# WristMountedAvionics.net
KiCad netlist of a schematic drawn in EasyEDA
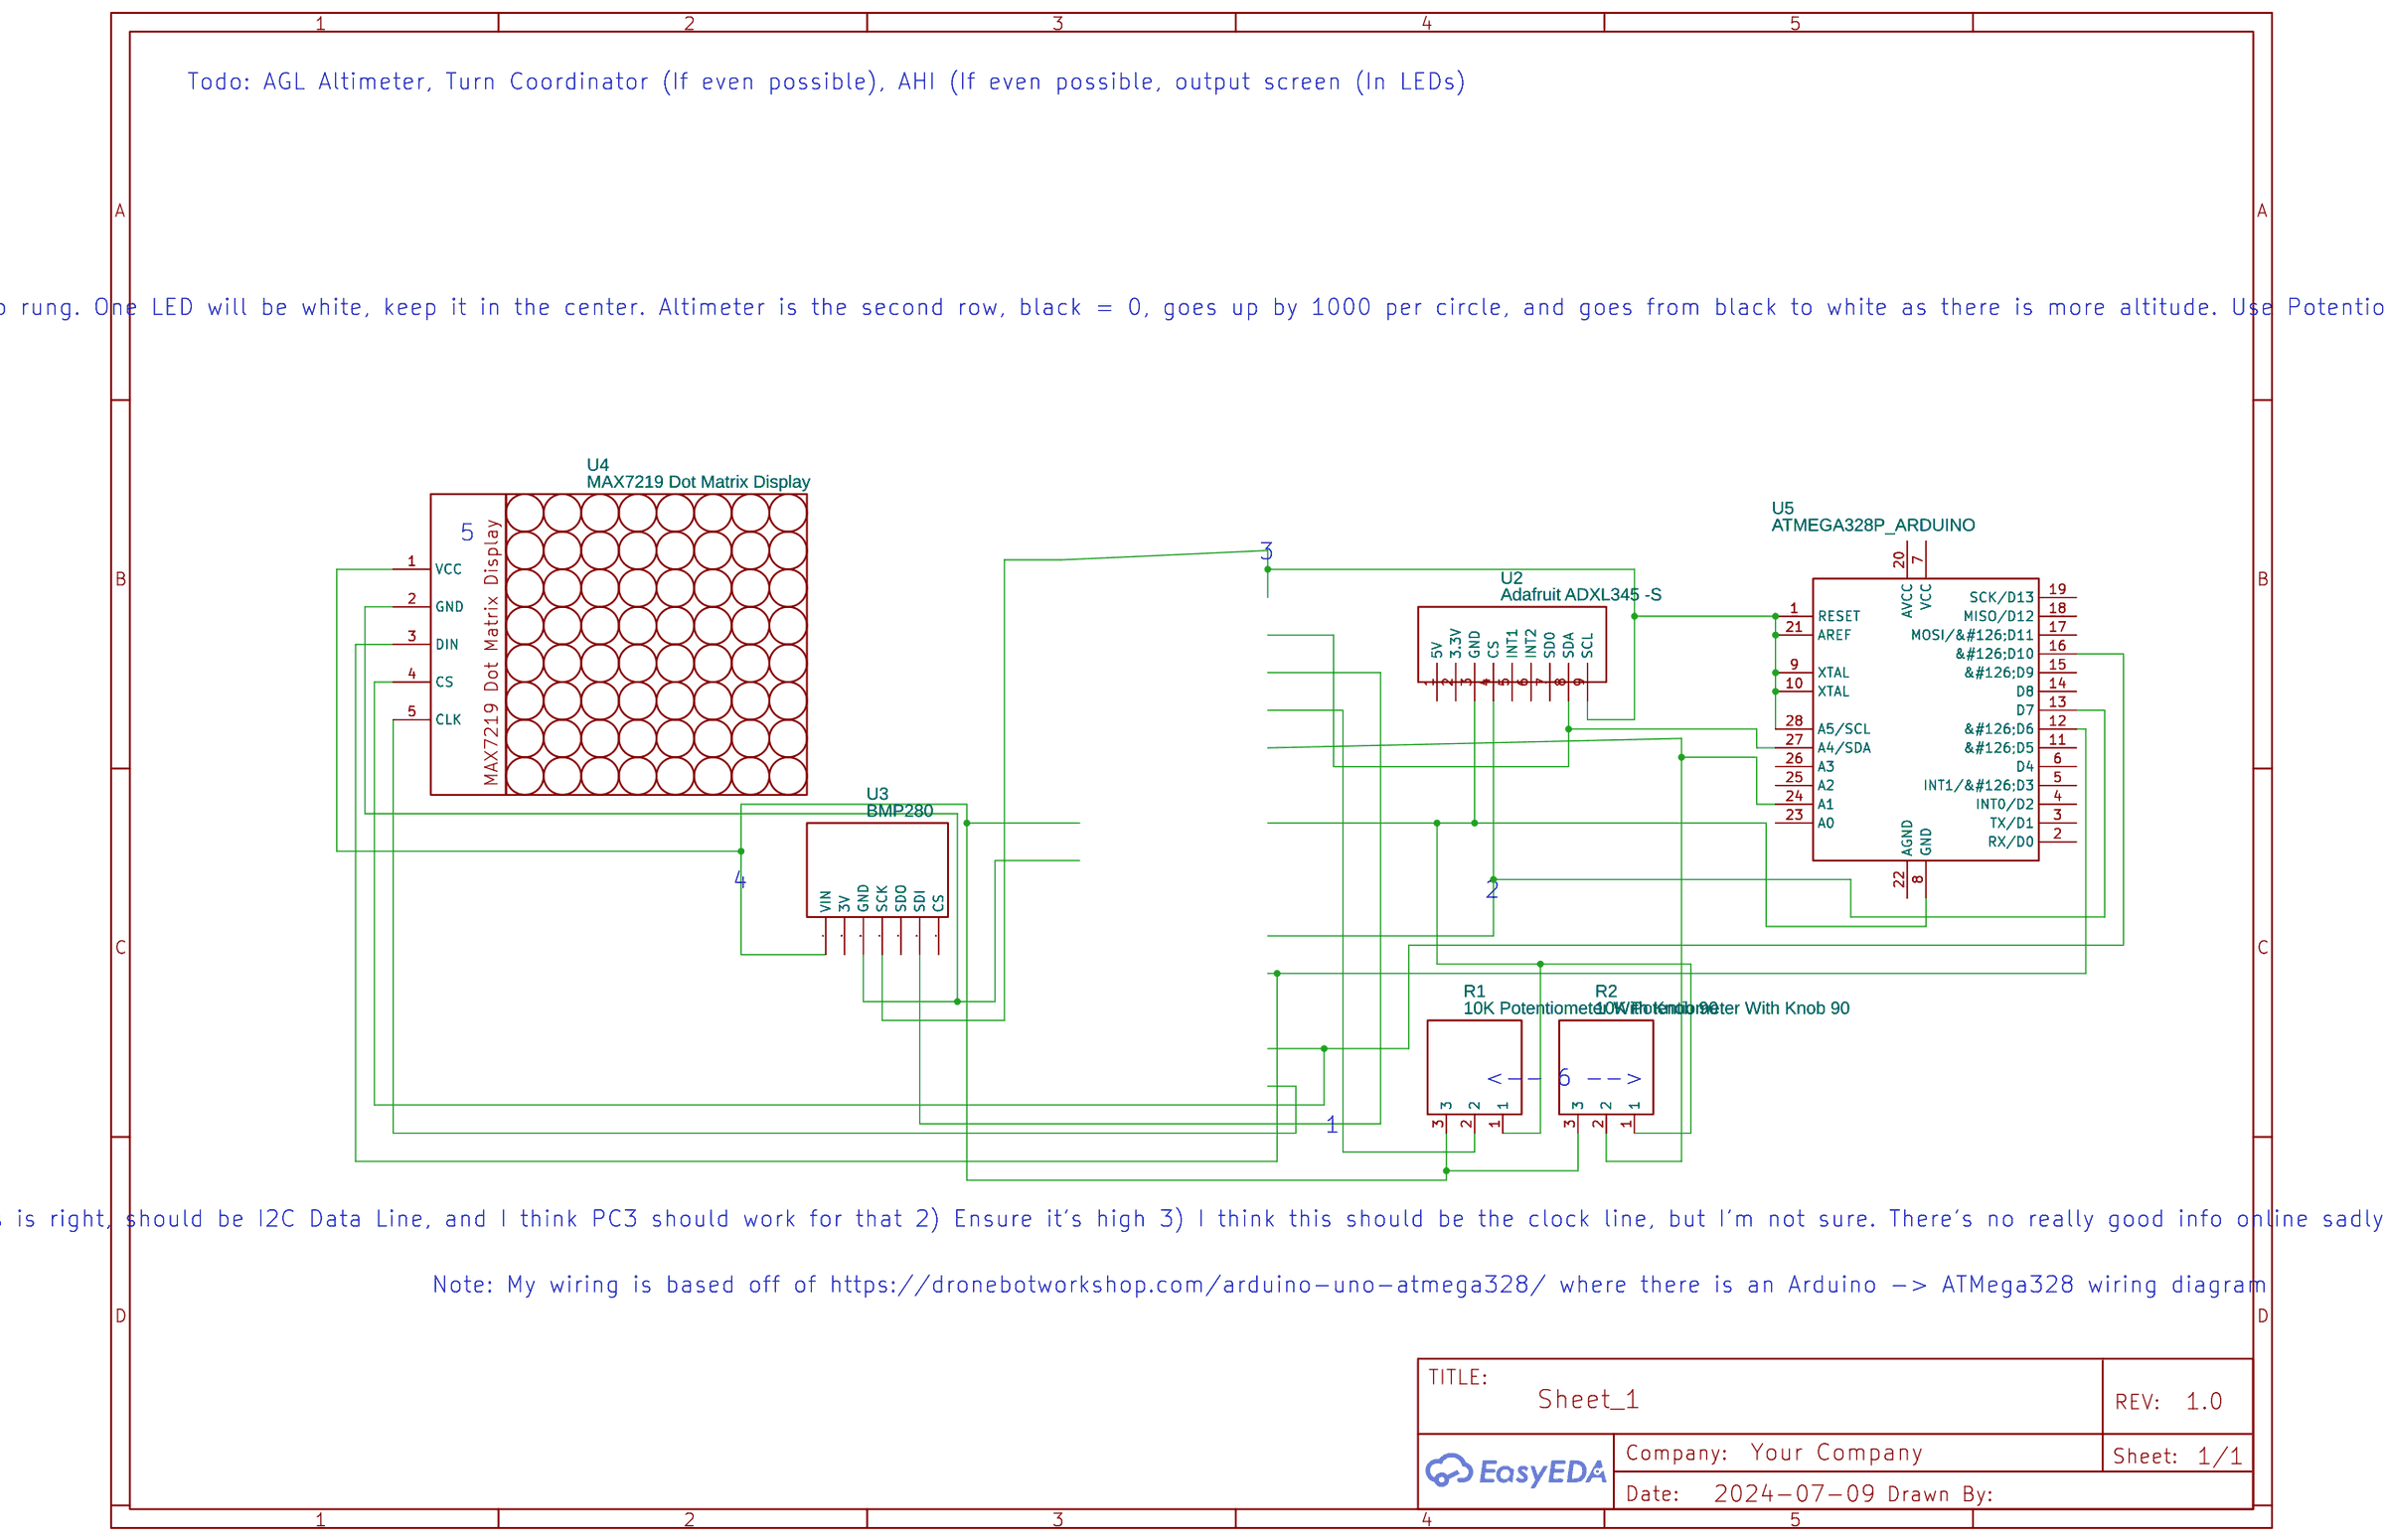
[diagram p0: schematic sheet]

(export (version "E")
  (design (tool "Eeschema 10.0.6"))
  (components
    (comp (ref "R1")
      (value "10K Potentiometer With Knob 90")
      (libsource (lib "") (part "10K-POTENTIOMETER COPY"))
    )
    (comp (ref "R2")
      (value "10K Potentiometer With Knob 90")
      (libsource (lib "") (part "10K-POTENTIOMETER COPY"))
    )
    (comp (ref "U2") (value "Adafruit ADXL345 -S") (libsource (lib "") (part "Adafruit ADXL345 -S")))
    (comp (ref "U3") (value "BMP280") (libsource (lib "") (part "BMP280")))
    (comp (ref "U4")
      (value "MAX7219 Dot Matrix Display")
      (libsource (lib "") (part "MAX7219 Dot Matrix Display"))
    )
    (comp (ref "U5") (value "ATMEGA328P_ARDUINO") (libsource (lib "") (part "ATMEGA328P_ARDUINO")))
  )
  (nets
    (net (code "1") (name "Net-(U2-CS)") (class "Default")
      (node (ref "U2") (pin "4") (pinfunction "CS_4") (pintype "unspecified"))
      (node (ref "U5") (pin "13") (pinfunction "D7_13") (pintype "unspecified"))
    )
    (net (code "2") (name "Net-(U2-GND)") (class "Default")
      (node (ref "R1") (pin "1") (pinfunction "1_1") (pintype "unspecified"))
      (node (ref "R2") (pin "1") (pinfunction "1_1") (pintype "unspecified"))
      (node (ref "U2") (pin "3") (pinfunction "GND_3") (pintype "unspecified"))
      (node (ref "U5") (pin "8") (pinfunction "GND_8") (pintype "unspecified"))
    )
    (net (code "3") (name "Net-(U2-SCL)") (class "Default")
      (node (ref "U2") (pin "9") (pinfunction "SCL_9") (pintype "unspecified"))
      (node (ref "U3") (pin "4") (pinfunction "SCK_4") (pintype "unspecified"))
      (node (ref "U5") (pin "1") (pinfunction "RESET_1") (pintype "unspecified"))
      (node (ref "U5") (pin "10") (pinfunction "XTAL_10") (pintype "unspecified"))
      (node (ref "U5") (pin "21") (pinfunction "AREF_21") (pintype "unspecified"))
      (node (ref "U5") (pin "28") (pinfunction "A5/SCL_28") (pintype "unspecified"))
      (node (ref "U5") (pin "9") (pinfunction "XTAL_9") (pintype "unspecified"))
    )
    (net (code "4") (name "Net-(U2-SDA)") (class "Default")
      (node (ref "U2") (pin "8") (pinfunction "SDA_8") (pintype "unspecified"))
      (node (ref "U5") (pin "27") (pinfunction "A4/SDA_27") (pintype "unspecified"))
    )
    (net (code "5") (name "Net-(U3-GND)") (class "Default")
      (node (ref "U3") (pin "5") (pinfunction "GND_5") (pintype "unspecified"))
      (node (ref "U4") (pin "2") (pinfunction "GND_2") (pintype "unspecified"))
    )
    (net (code "6") (name "Net-(U3-VIN)") (class "Default")
      (node (ref "R1") (pin "3") (pinfunction "3_3") (pintype "unspecified"))
      (node (ref "R2") (pin "3") (pinfunction "3_3") (pintype "unspecified"))
      (node (ref "U3") (pin "7") (pinfunction "VIN_7") (pintype "unspecified"))
      (node (ref "U4") (pin "1") (pinfunction "VCC_1") (pintype "unspecified"))
    )
    (net (code "7") (name "Net-(U4-CS)") (class "Default")
      (node (ref "U4") (pin "4") (pinfunction "CS_4") (pintype "unspecified"))
      (node (ref "U5") (pin "16") (pinfunction "&#126;D10_16") (pintype "unspecified"))
    )
    (net (code "8") (name "Net-(U4-DIN)") (class "Default")
      (node (ref "U4") (pin "3") (pinfunction "DIN_3") (pintype "unspecified"))
      (node (ref "U5") (pin "12") (pinfunction "&#126;D6_12") (pintype "unspecified"))
    )
    (net (code "9") (name "Net-(U5-A1)") (class "Default")
      (node (ref "R2") (pin "2") (pinfunction "2_2") (pintype "unspecified"))
      (node (ref "U5") (pin "24") (pinfunction "A1_24") (pintype "unspecified"))
    )
    (net (code "10") (name "unconnected-(R1-Pad2)") (class "Default")
      (node (ref "R1") (pin "2") (pinfunction "2_2") (pintype "unspecified"))
    )
    (net (code "11") (name "unconnected-(U2-3.3V-Pad2)") (class "Default")
      (node (ref "U2") (pin "2") (pinfunction "3.3V_2") (pintype "unspecified"))
    )
    (net (code "12") (name "unconnected-(U2-5V-Pad1)") (class "Default")
      (node (ref "U2") (pin "1") (pinfunction "5V_1") (pintype "unspecified"))
    )
    (net (code "13") (name "unconnected-(U2-INT1-Pad5)") (class "Default")
      (node (ref "U2") (pin "5") (pinfunction "INT1_5") (pintype "unspecified"))
    )
    (net (code "14") (name "unconnected-(U2-INT2-Pad6)") (class "Default")
      (node (ref "U2") (pin "6") (pinfunction "INT2_6") (pintype "unspecified"))
    )
    (net (code "15") (name "unconnected-(U2-SD0-Pad7)") (class "Default")
      (node (ref "U2") (pin "7") (pinfunction "SD0_7") (pintype "unspecified"))
    )
    (net (code "16") (name "unconnected-(U3-3V-Pad6)") (class "Default")
      (node (ref "U3") (pin "6") (pinfunction "3V_6") (pintype "unspecified"))
    )
    (net (code "17") (name "unconnected-(U3-CS-Pad1)") (class "Default")
      (node (ref "U3") (pin "1") (pinfunction "CS_1") (pintype "unspecified"))
    )
    (net (code "18") (name "unconnected-(U3-SDI-Pad2)") (class "Default")
      (node (ref "U3") (pin "2") (pinfunction "SDI_2") (pintype "unspecified"))
    )
    (net (code "19") (name "unconnected-(U3-SDO-Pad3)") (class "Default")
      (node (ref "U3") (pin "3") (pinfunction "SDO_3") (pintype "unspecified"))
    )
    (net (code "20") (name "unconnected-(U4-CLK-Pad5)") (class "Default")
      (node (ref "U4") (pin "5") (pinfunction "CLK_5") (pintype "unspecified"))
    )
    (net (code "21") (name "unconnected-(U5-&#126;D5-Pad11)") (class "Default")
      (node (ref "U5") (pin "11") (pinfunction "&#126;D5_11") (pintype "unspecified"))
    )
    (net (code "22") (name "unconnected-(U5-&#126;D9-Pad15)") (class "Default")
      (node (ref "U5") (pin "15") (pinfunction "&#126;D9_15") (pintype "unspecified"))
    )
    (net (code "23") (name "unconnected-(U5-A0-Pad23)") (class "Default")
      (node (ref "U5") (pin "23") (pinfunction "A0_23") (pintype "unspecified"))
    )
    (net (code "24") (name "unconnected-(U5-A2-Pad25)") (class "Default")
      (node (ref "U5") (pin "25") (pinfunction "A2_25") (pintype "unspecified"))
    )
    (net (code "25") (name "unconnected-(U5-A3-Pad26)") (class "Default")
      (node (ref "U5") (pin "26") (pinfunction "A3_26") (pintype "unspecified"))
    )
    (net (code "26") (name "unconnected-(U5-AGND-Pad22)") (class "Default")
      (node (ref "U5") (pin "22") (pinfunction "AGND_22") (pintype "unspecified"))
    )
    (net (code "27") (name "unconnected-(U5-AVCC-Pad20)") (class "Default")
      (node (ref "U5") (pin "20") (pinfunction "AVCC_20") (pintype "unspecified"))
    )
    (net (code "28") (name "unconnected-(U5-D4-Pad6)") (class "Default")
      (node (ref "U5") (pin "6") (pinfunction "D4_6") (pintype "unspecified"))
    )
    (net (code "29") (name "unconnected-(U5-D8-Pad14)") (class "Default")
      (node (ref "U5") (pin "14") (pinfunction "D8_14") (pintype "unspecified"))
    )
    (net (code "30") (name "unconnected-(U5-INT0{slash}D2-Pad4)") (class "Default")
      (node (ref "U5") (pin "4") (pinfunction "INT0/D2_4") (pintype "unspecified"))
    )
    (net (code "31") (name "unconnected-(U5-INT1{slash}&#126;D3-Pad5)") (class "Default")
      (node (ref "U5") (pin "5") (pinfunction "INT1/&#126;D3_5") (pintype "unspecified"))
    )
    (net (code "32") (name "unconnected-(U5-MISO{slash}D12-Pad18)") (class "Default")
      (node (ref "U5") (pin "18") (pinfunction "MISO/D12_18") (pintype "unspecified"))
    )
    (net (code "33") (name "unconnected-(U5-MOSI{slash}&#126;D11-Pad17)") (class "Default")
      (node (ref "U5") (pin "17") (pinfunction "MOSI/&#126;D11_17") (pintype "unspecified"))
    )
    (net (code "34") (name "unconnected-(U5-RX{slash}D0-Pad2)") (class "Default")
      (node (ref "U5") (pin "2") (pinfunction "RX/D0_2") (pintype "unspecified"))
    )
    (net (code "35") (name "unconnected-(U5-SCK{slash}D13-Pad19)") (class "Default")
      (node (ref "U5") (pin "19") (pinfunction "SCK/D13_19") (pintype "unspecified"))
    )
    (net (code "36") (name "unconnected-(U5-TX{slash}D1-Pad3)") (class "Default")
      (node (ref "U5") (pin "3") (pinfunction "TX/D1_3") (pintype "unspecified"))
    )
    (net (code "37") (name "unconnected-(U5-VCC-Pad7)") (class "Default")
      (node (ref "U5") (pin "7") (pinfunction "VCC_7") (pintype "unspecified"))
    )
  )
)
